# SCH_s2PC_2024-04-20.net
KiCad netlist of a schematic drawn in EasyEDA
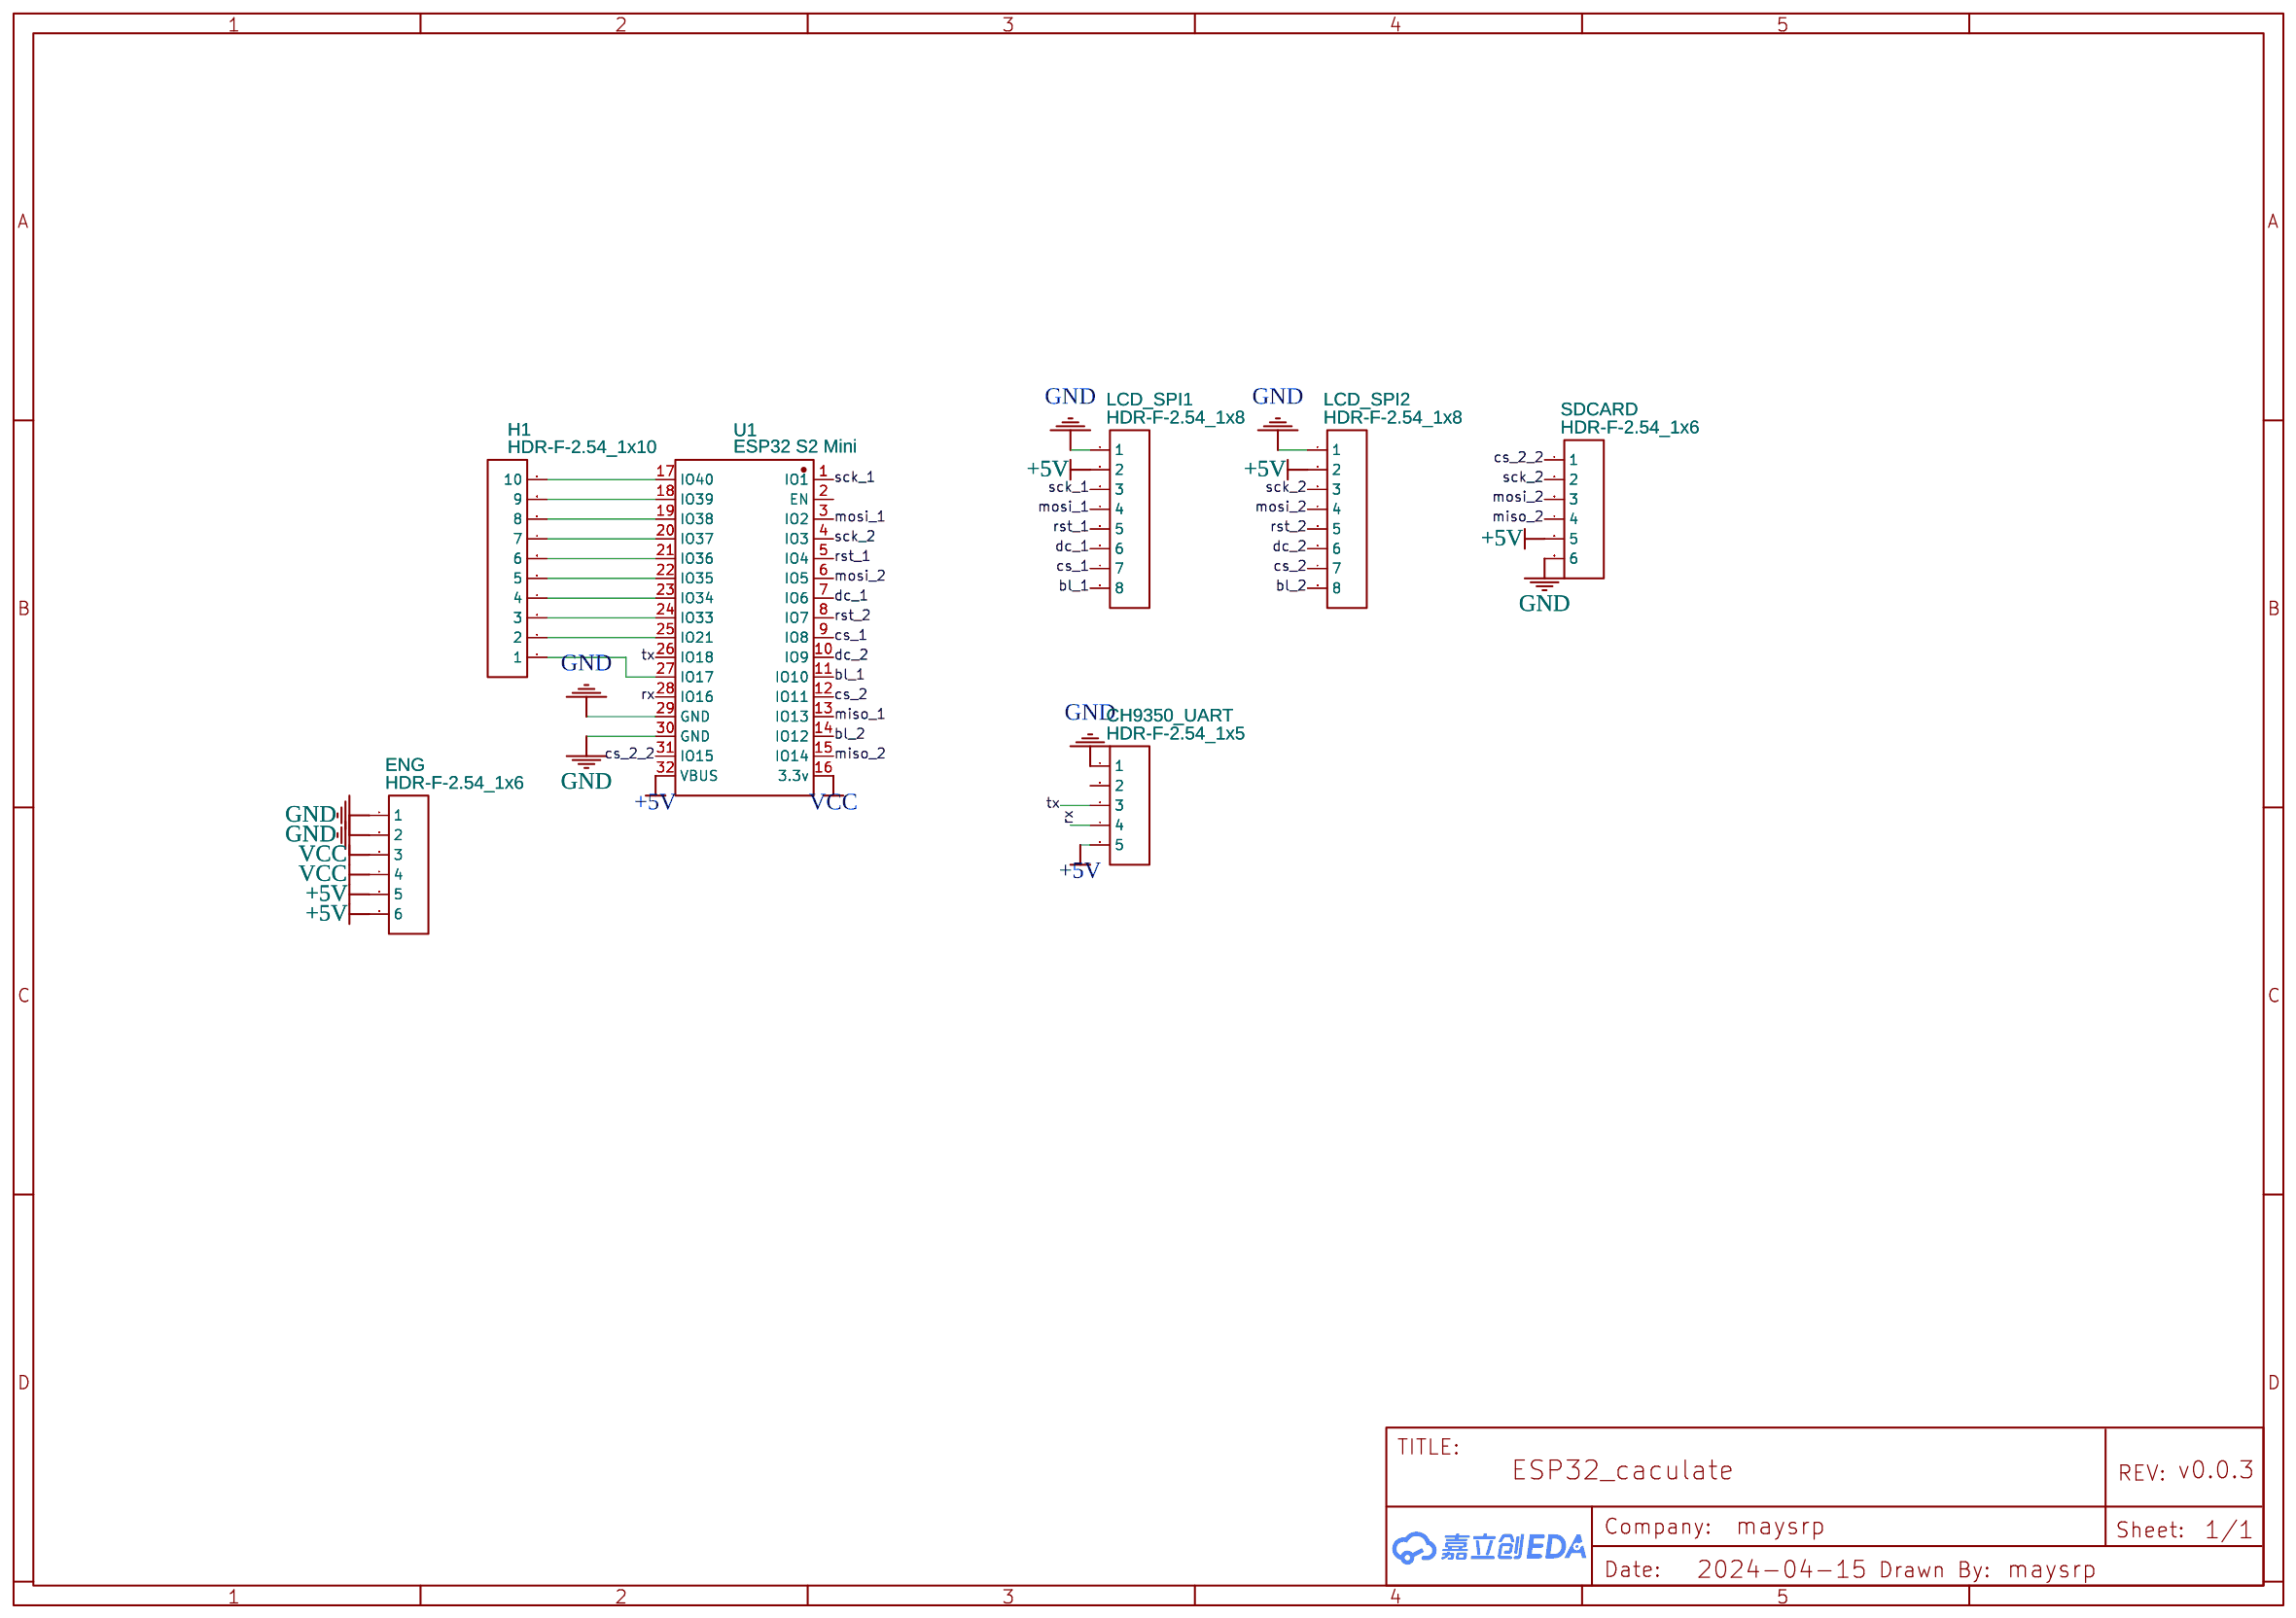
[diagram p0: schematic sheet]

(export (version "E")
  (design (tool "Eeschema 10.0.6"))
  (components
    (comp (ref "CH9350_UART") (value "HDR-F-2.54_1x5") (libsource (lib "") (part "HDR-F-2.54_1x5")))
    (comp (ref "ENG") (value "HDR-F-2.54_1x6") (libsource (lib "") (part "HDR-F-2.54_1x6_1")))
    (comp (ref "H1") (value "HDR-F-2.54_1x10") (libsource (lib "") (part "HDR-F-2.54_1x10")))
    (comp (ref "LCD_SPI1") (value "HDR-F-2.54_1x8") (libsource (lib "") (part "HDR-F-2.54_1x8")))
    (comp (ref "LCD_SPI2") (value "HDR-F-2.54_1x8") (libsource (lib "") (part "HDR-F-2.54_1x8")))
    (comp (ref "SDCARD") (value "HDR-F-2.54_1x6") (libsource (lib "") (part "HDR-F-2.54_1x6")))
    (comp (ref "U1") (value "ESP32 S2 Mini") (libsource (lib "") (part "ESP32 S2 Mini")))
  )
  (nets
    (net (code "1") (name "+5V") (class "Default")
      (node (ref "CH9350_UART") (pin "5") (pinfunction "5_5") (pintype "unspecified"))
      (node (ref "ENG") (pin "5") (pinfunction "5_5") (pintype "input"))
      (node (ref "ENG") (pin "6") (pinfunction "6_6") (pintype "input"))
      (node (ref "LCD_SPI1") (pin "2") (pinfunction "2_2") (pintype "unspecified"))
      (node (ref "LCD_SPI2") (pin "2") (pinfunction "2_2") (pintype "unspecified"))
      (node (ref "SDCARD") (pin "5") (pinfunction "5_5") (pintype "input"))
      (node (ref "U1") (pin "32") (pinfunction "VBUS_32") (pintype "unspecified"))
    )
    (net (code "2") (name "/bl_1") (class "Default")
      (node (ref "LCD_SPI1") (pin "8") (pinfunction "8_8") (pintype "unspecified"))
      (node (ref "U1") (pin "11") (pinfunction "IO10_11") (pintype "unspecified"))
    )
    (net (code "3") (name "/bl_2") (class "Default")
      (node (ref "LCD_SPI2") (pin "8") (pinfunction "8_8") (pintype "unspecified"))
      (node (ref "U1") (pin "14") (pinfunction "IO12_14") (pintype "unspecified"))
    )
    (net (code "4") (name "/cs_1") (class "Default")
      (node (ref "LCD_SPI1") (pin "7") (pinfunction "7_7") (pintype "unspecified"))
      (node (ref "U1") (pin "9") (pinfunction "IO8_9") (pintype "unspecified"))
    )
    (net (code "5") (name "/cs_2") (class "Default")
      (node (ref "LCD_SPI2") (pin "7") (pinfunction "7_7") (pintype "unspecified"))
      (node (ref "U1") (pin "12") (pinfunction "IO11_12") (pintype "unspecified"))
    )
    (net (code "6") (name "/cs_2_2") (class "Default")
      (node (ref "SDCARD") (pin "1") (pinfunction "1_1") (pintype "input"))
      (node (ref "U1") (pin "31") (pinfunction "IO15_31") (pintype "unspecified"))
    )
    (net (code "7") (name "/dc_1") (class "Default")
      (node (ref "LCD_SPI1") (pin "6") (pinfunction "6_6") (pintype "unspecified"))
      (node (ref "U1") (pin "7") (pinfunction "IO6_7") (pintype "unspecified"))
    )
    (net (code "8") (name "/dc_2") (class "Default")
      (node (ref "LCD_SPI2") (pin "6") (pinfunction "6_6") (pintype "unspecified"))
      (node (ref "U1") (pin "10") (pinfunction "IO9_10") (pintype "unspecified"))
    )
    (net (code "9") (name "/miso_1") (class "Default")
      (node (ref "U1") (pin "13") (pinfunction "IO13_13") (pintype "unspecified"))
    )
    (net (code "10") (name "/miso_2") (class "Default")
      (node (ref "SDCARD") (pin "4") (pinfunction "4_4") (pintype "input"))
      (node (ref "U1") (pin "15") (pinfunction "IO14_15") (pintype "unspecified"))
    )
    (net (code "11") (name "/mosi_1") (class "Default")
      (node (ref "LCD_SPI1") (pin "4") (pinfunction "4_4") (pintype "unspecified"))
      (node (ref "U1") (pin "3") (pinfunction "IO2_3") (pintype "unspecified"))
    )
    (net (code "12") (name "/mosi_2") (class "Default")
      (node (ref "LCD_SPI2") (pin "4") (pinfunction "4_4") (pintype "unspecified"))
      (node (ref "SDCARD") (pin "3") (pinfunction "3_3") (pintype "input"))
      (node (ref "U1") (pin "6") (pinfunction "IO5_6") (pintype "unspecified"))
    )
    (net (code "13") (name "/rst_1") (class "Default")
      (node (ref "LCD_SPI1") (pin "5") (pinfunction "5_5") (pintype "unspecified"))
      (node (ref "U1") (pin "5") (pinfunction "IO4_5") (pintype "unspecified"))
    )
    (net (code "14") (name "/rst_2") (class "Default")
      (node (ref "LCD_SPI2") (pin "5") (pinfunction "5_5") (pintype "unspecified"))
      (node (ref "U1") (pin "8") (pinfunction "IO7_8") (pintype "unspecified"))
    )
    (net (code "15") (name "/rx") (class "Default")
      (node (ref "CH9350_UART") (pin "4") (pinfunction "4_4") (pintype "unspecified"))
      (node (ref "U1") (pin "28") (pinfunction "IO16_28") (pintype "unspecified"))
    )
    (net (code "16") (name "/sck_1") (class "Default")
      (node (ref "LCD_SPI1") (pin "3") (pinfunction "3_3") (pintype "unspecified"))
      (node (ref "U1") (pin "1") (pinfunction "IO1_1") (pintype "unspecified"))
    )
    (net (code "17") (name "/sck_2") (class "Default")
      (node (ref "LCD_SPI2") (pin "3") (pinfunction "3_3") (pintype "unspecified"))
      (node (ref "SDCARD") (pin "2") (pinfunction "2_2") (pintype "input"))
      (node (ref "U1") (pin "4") (pinfunction "IO3_4") (pintype "unspecified"))
    )
    (net (code "18") (name "/tx") (class "Default")
      (node (ref "CH9350_UART") (pin "3") (pinfunction "3_3") (pintype "unspecified"))
      (node (ref "U1") (pin "26") (pinfunction "IO18_26") (pintype "unspecified"))
    )
    (net (code "19") (name "GND") (class "Default")
      (node (ref "CH9350_UART") (pin "1") (pinfunction "1_1") (pintype "unspecified"))
      (node (ref "ENG") (pin "1") (pinfunction "1_1") (pintype "input"))
      (node (ref "ENG") (pin "2") (pinfunction "2_2") (pintype "input"))
      (node (ref "LCD_SPI1") (pin "1") (pinfunction "1_1") (pintype "unspecified"))
      (node (ref "LCD_SPI2") (pin "1") (pinfunction "1_1") (pintype "unspecified"))
      (node (ref "SDCARD") (pin "6") (pinfunction "6_6") (pintype "input"))
      (node (ref "U1") (pin "29") (pinfunction "GND_29") (pintype "unspecified"))
      (node (ref "U1") (pin "30") (pinfunction "GND_30") (pintype "unspecified"))
    )
    (net (code "20") (name "Net-(U1-IO17)") (class "Default")
      (node (ref "H1") (pin "1") (pinfunction "1_1") (pintype "unspecified"))
      (node (ref "U1") (pin "27") (pinfunction "IO17_27") (pintype "unspecified"))
    )
    (net (code "21") (name "Net-(U1-IO21)") (class "Default")
      (node (ref "H1") (pin "2") (pinfunction "2_2") (pintype "unspecified"))
      (node (ref "U1") (pin "25") (pinfunction "IO21_25") (pintype "unspecified"))
    )
    (net (code "22") (name "Net-(U1-IO33)") (class "Default")
      (node (ref "H1") (pin "3") (pinfunction "3_3") (pintype "unspecified"))
      (node (ref "U1") (pin "24") (pinfunction "IO33_24") (pintype "unspecified"))
    )
    (net (code "23") (name "Net-(U1-IO34)") (class "Default")
      (node (ref "H1") (pin "4") (pinfunction "4_4") (pintype "unspecified"))
      (node (ref "U1") (pin "23") (pinfunction "IO34_23") (pintype "unspecified"))
    )
    (net (code "24") (name "Net-(U1-IO35)") (class "Default")
      (node (ref "H1") (pin "5") (pinfunction "5_5") (pintype "unspecified"))
      (node (ref "U1") (pin "22") (pinfunction "IO35_22") (pintype "unspecified"))
    )
    (net (code "25") (name "Net-(U1-IO36)") (class "Default")
      (node (ref "H1") (pin "6") (pinfunction "6_6") (pintype "unspecified"))
      (node (ref "U1") (pin "21") (pinfunction "IO36_21") (pintype "unspecified"))
    )
    (net (code "26") (name "Net-(U1-IO37)") (class "Default")
      (node (ref "H1") (pin "7") (pinfunction "7_7") (pintype "unspecified"))
      (node (ref "U1") (pin "20") (pinfunction "IO37_20") (pintype "unspecified"))
    )
    (net (code "27") (name "Net-(U1-IO38)") (class "Default")
      (node (ref "H1") (pin "8") (pinfunction "8_8") (pintype "unspecified"))
      (node (ref "U1") (pin "19") (pinfunction "IO38_19") (pintype "unspecified"))
    )
    (net (code "28") (name "Net-(U1-IO39)") (class "Default")
      (node (ref "H1") (pin "9") (pinfunction "9_9") (pintype "unspecified"))
      (node (ref "U1") (pin "18") (pinfunction "IO39_18") (pintype "unspecified"))
    )
    (net (code "29") (name "Net-(U1-IO40)") (class "Default")
      (node (ref "H1") (pin "10") (pinfunction "10_10") (pintype "unspecified"))
      (node (ref "U1") (pin "17") (pinfunction "IO40_17") (pintype "unspecified"))
    )
    (net (code "30") (name "VCC") (class "Default")
      (node (ref "ENG") (pin "3") (pinfunction "3_3") (pintype "input"))
      (node (ref "ENG") (pin "4") (pinfunction "4_4") (pintype "input"))
      (node (ref "U1") (pin "16") (pinfunction "3.3v_16") (pintype "unspecified"))
    )
    (net (code "31") (name "unconnected-(CH9350_UART-Pad2)") (class "Default")
      (node (ref "CH9350_UART") (pin "2") (pinfunction "2_2") (pintype "unspecified"))
    )
    (net (code "32") (name "unconnected-(U1-EN-Pad2)") (class "Default")
      (node (ref "U1") (pin "2") (pinfunction "EN_2") (pintype "unspecified"))
    )
  )
)
